# PC104-52-52.net
KiCad netlist of a schematic drawn in Altium Designer
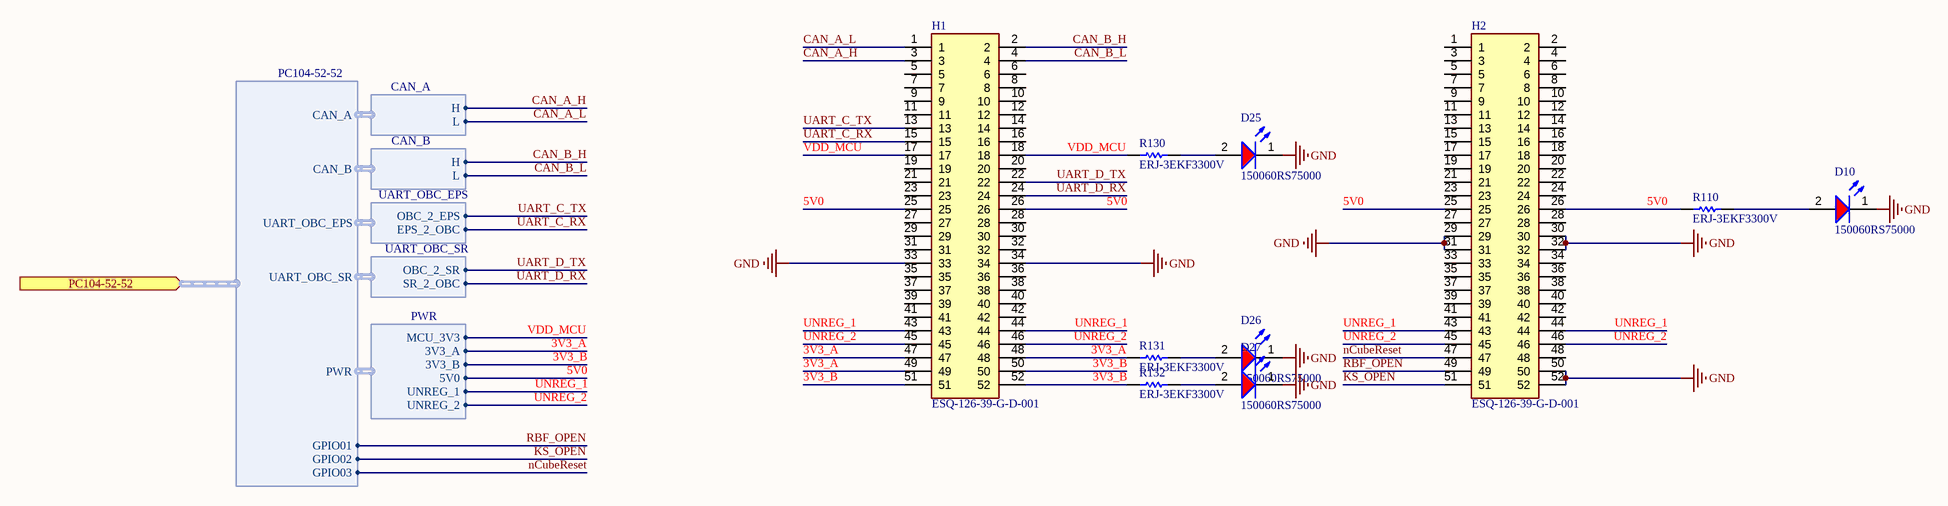
[diagram p0: PC104-52-52.SchDoc]

(export (version "E")
  (design (tool "Eeschema 10.0.6"))
  (components
    (comp (ref "D10")
      (value "150060RS75000")
      (footprint "WL-SMCW_0603_150060xx75000")
      (description "LED Low-Power Uni-Color Red 630nm 2V 2-Pin Chip 0603(1608Metric) T/R")
      (libsource (lib "Altium Content Vault") (part "LED_Red_2A-1K"))
    )
    (comp (ref "D25")
      (value "150060RS75000")
      (footprint "WL-SMCW_0603_150060xx75000")
      (description "LED Low-Power Uni-Color Red 630nm 2V 2-Pin Chip 0603(1608Metric) T/R")
      (libsource (lib "Altium Content Vault") (part "LED_Red_2A-1K"))
    )
    (comp (ref "D26")
      (value "150060RS75000")
      (footprint "WL-SMCW_0603_150060xx75000")
      (description "LED Low-Power Uni-Color Red 630nm 2V 2-Pin Chip 0603(1608Metric) T/R")
      (libsource (lib "Altium Content Vault") (part "LED_Red_2A-1K"))
    )
    (comp (ref "D27")
      (value "150060RS75000")
      (footprint "WL-SMCW_0603_150060xx75000")
      (description "LED Low-Power Uni-Color Red 630nm 2V 2-Pin Chip 0603(1608Metric) T/R")
      (libsource (lib "Altium Content Vault") (part "LED_Red_2A-1K"))
    )
    (comp (ref "H1")
      (value "ESQ-126-39-G-D-001")
      (footprint "RHDR52W64P254_2X26_6654X495X1135P")
      (description "PC / 104 Connectors Elevated Socket Strip")
      (fields (field (name "MOUSER PART NUMBER") "200-ESQ12639GD001"))
      (libsource (lib "Hitesh Bhoyar") (part "ESQ-126-39-G-D-001"))
    )
    (comp (ref "H2")
      (value "ESQ-126-39-G-D-001")
      (footprint "RHDR52W64P254_2X26_6654X495X1135P")
      (description "PC / 104 Connectors Elevated Socket Strip")
      (fields (field (name "MOUSER PART NUMBER") "200-ESQ12639GD001"))
      (libsource (lib "Hitesh Bhoyar") (part "ESQ-126-39-G-D-001"))
    )
    (comp (ref "R110")
      (value "ERJ-3EKF3300V")
      (footprint "RESC1608X55X30LL15T15")
      (description "Chip Resistor, 330 Ohm, +/- 1%, 0.1 W, -55 to 155 degC, 0603 (1608 Metric), RoHS, Tape and Reel")
      (libsource (lib "Altium Content Vault") (part "RES-2"))
    )
    (comp (ref "R130")
      (value "ERJ-3EKF3300V")
      (footprint "RESC1608X55X30LL15T15")
      (description "Chip Resistor, 330 Ohm, +/- 1%, 0.1 W, -55 to 155 degC, 0603 (1608 Metric), RoHS, Tape and Reel")
      (libsource (lib "Altium Content Vault") (part "RES-2"))
    )
    (comp (ref "R131")
      (value "ERJ-3EKF3300V")
      (footprint "RESC1608X55X30LL15T15")
      (description "Chip Resistor, 330 Ohm, +/- 1%, 0.1 W, -55 to 155 degC, 0603 (1608 Metric), RoHS, Tape and Reel")
      (libsource (lib "Altium Content Vault") (part "RES-2"))
    )
    (comp (ref "R132")
      (value "ERJ-3EKF3300V")
      (footprint "RESC1608X55X30LL15T15")
      (description "Chip Resistor, 330 Ohm, +/- 1%, 0.1 W, -55 to 155 degC, 0603 (1608 Metric), RoHS, Tape and Reel")
      (libsource (lib "Altium Content Vault") (part "RES-2"))
    )
  )
  (nets
    (net (code "7") (name "/3V3_A") (class "Default")
      (node (ref "H1") (pin "47") (pinfunction "47_47") (pintype "passive"))
      (node (ref "H1") (pin "48") (pinfunction "48_48") (pintype "passive"))
      (node (ref "H1") (pin "49") (pinfunction "49_49") (pintype "passive"))
      (node (ref "R131") (pin "1") (pinfunction "1_1") (pintype "passive"))
    )
    (net (code "8") (name "/3V3_B") (class "Default")
      (node (ref "H1") (pin "50") (pinfunction "50_50") (pintype "passive"))
      (node (ref "H1") (pin "51") (pinfunction "51_51") (pintype "passive"))
      (node (ref "H1") (pin "52") (pinfunction "52_52") (pintype "passive"))
      (node (ref "R132") (pin "1") (pinfunction "1_1") (pintype "passive"))
    )
    (net (code "9") (name "/5V0") (class "Default")
      (node (ref "H1") (pin "25") (pinfunction "25_25") (pintype "passive"))
      (node (ref "H1") (pin "26") (pinfunction "26_26") (pintype "passive"))
      (node (ref "H2") (pin "25") (pinfunction "25_25") (pintype "passive"))
      (node (ref "H2") (pin "26") (pinfunction "26_26") (pintype "passive"))
      (node (ref "R110") (pin "1") (pinfunction "1_1") (pintype "passive"))
    )
    (net (code "10") (name "/CAN_A_H") (class "Default")
      (node (ref "H1") (pin "3") (pinfunction "3_3") (pintype "passive"))
    )
    (net (code "11") (name "/CAN_A_L") (class "Default")
      (node (ref "H1") (pin "1") (pinfunction "1_1") (pintype "passive"))
    )
    (net (code "12") (name "/CAN_B_H") (class "Default")
      (node (ref "H1") (pin "2") (pinfunction "2_2") (pintype "passive"))
    )
    (net (code "13") (name "/CAN_B_L") (class "Default")
      (node (ref "H1") (pin "4") (pinfunction "4_4") (pintype "passive"))
    )
    (net (code "14") (name "/KS_OPEN") (class "Default")
      (node (ref "H2") (pin "51") (pinfunction "51_51") (pintype "passive"))
    )
    (net (code "16") (name "/RBF_OPEN") (class "Default")
      (node (ref "H2") (pin "49") (pinfunction "49_49") (pintype "passive"))
    )
    (net (code "17") (name "/UART_C_RX") (class "Default")
      (node (ref "H1") (pin "15") (pinfunction "15_15") (pintype "passive"))
    )
    (net (code "18") (name "/UART_C_TX") (class "Default")
      (node (ref "H1") (pin "13") (pinfunction "13_13") (pintype "passive"))
    )
    (net (code "19") (name "/UART_D_RX") (class "Default")
      (node (ref "H1") (pin "24") (pinfunction "24_24") (pintype "passive"))
    )
    (net (code "20") (name "/UART_D_TX") (class "Default")
      (node (ref "H1") (pin "22") (pinfunction "22_22") (pintype "passive"))
    )
    (net (code "21") (name "/UNREG_1") (class "Default")
      (node (ref "H1") (pin "43") (pinfunction "43_43") (pintype "passive"))
      (node (ref "H1") (pin "44") (pinfunction "44_44") (pintype "passive"))
      (node (ref "H2") (pin "43") (pinfunction "43_43") (pintype "passive"))
      (node (ref "H2") (pin "44") (pinfunction "44_44") (pintype "passive"))
    )
    (net (code "22") (name "/UNREG_2") (class "Default")
      (node (ref "H1") (pin "45") (pinfunction "45_45") (pintype "passive"))
      (node (ref "H1") (pin "46") (pinfunction "46_46") (pintype "passive"))
      (node (ref "H2") (pin "45") (pinfunction "45_45") (pintype "passive"))
      (node (ref "H2") (pin "46") (pinfunction "46_46") (pintype "passive"))
    )
    (net (code "23") (name "/VDD_MCU") (class "Default")
      (node (ref "H1") (pin "17") (pinfunction "17_17") (pintype "passive"))
      (node (ref "H1") (pin "18") (pinfunction "18_18") (pintype "passive"))
      (node (ref "R130") (pin "1") (pinfunction "1_1") (pintype "passive"))
    )
    (net (code "24") (name "/nCubeReset") (class "Default")
      (node (ref "H2") (pin "47") (pinfunction "47_47") (pintype "passive"))
    )
    (net (code "30") (name "GND") (class "Default")
      (node (ref "D10") (pin "1") (pinfunction "K_1") (pintype "passive"))
      (node (ref "D25") (pin "1") (pinfunction "K_1") (pintype "passive"))
      (node (ref "D26") (pin "1") (pinfunction "K_1") (pintype "passive"))
      (node (ref "D27") (pin "1") (pinfunction "K_1") (pintype "passive"))
      (node (ref "H1") (pin "33") (pinfunction "33_33") (pintype "passive"))
      (node (ref "H1") (pin "34") (pinfunction "34_34") (pintype "passive"))
      (node (ref "H2") (pin "29") (pinfunction "29_29") (pintype "passive"))
      (node (ref "H2") (pin "30") (pinfunction "30_30") (pintype "passive"))
      (node (ref "H2") (pin "31") (pinfunction "31_31") (pintype "passive"))
      (node (ref "H2") (pin "32") (pinfunction "32_32") (pintype "passive"))
      (node (ref "H2") (pin "50") (pinfunction "50_50") (pintype "passive"))
      (node (ref "H2") (pin "52") (pinfunction "52_52") (pintype "passive"))
    )
    (net (code "31") (name "Net-(D10-A)") (class "Default")
      (node (ref "D10") (pin "2") (pinfunction "A_2") (pintype "passive"))
      (node (ref "R110") (pin "2") (pinfunction "2_2") (pintype "passive"))
    )
    (net (code "32") (name "Net-(D25-A)") (class "Default")
      (node (ref "D25") (pin "2") (pinfunction "A_2") (pintype "passive"))
      (node (ref "R130") (pin "2") (pinfunction "2_2") (pintype "passive"))
    )
    (net (code "33") (name "Net-(D26-A)") (class "Default")
      (node (ref "D26") (pin "2") (pinfunction "A_2") (pintype "passive"))
      (node (ref "R131") (pin "2") (pinfunction "2_2") (pintype "passive"))
    )
    (net (code "34") (name "Net-(D27-A)") (class "Default")
      (node (ref "D27") (pin "2") (pinfunction "A_2") (pintype "passive"))
      (node (ref "R132") (pin "2") (pinfunction "2_2") (pintype "passive"))
    )
    (net (code "35") (name "unconnected-(H1-Pad5)") (class "Default")
      (node (ref "H1") (pin "5") (pinfunction "5_5") (pintype "passive"))
    )
    (net (code "36") (name "unconnected-(H1-Pad6)") (class "Default")
      (node (ref "H1") (pin "6") (pinfunction "6_6") (pintype "passive"))
    )
    (net (code "37") (name "unconnected-(H1-Pad7)") (class "Default")
      (node (ref "H1") (pin "7") (pinfunction "7_7") (pintype "passive"))
    )
    (net (code "38") (name "unconnected-(H1-Pad8)") (class "Default")
      (node (ref "H1") (pin "8") (pinfunction "8_8") (pintype "passive"))
    )
    (net (code "39") (name "unconnected-(H1-Pad9)") (class "Default")
      (node (ref "H1") (pin "9") (pinfunction "9_9") (pintype "passive"))
    )
    (net (code "40") (name "unconnected-(H1-Pad10)") (class "Default")
      (node (ref "H1") (pin "10") (pinfunction "10_10") (pintype "passive"))
    )
    (net (code "41") (name "unconnected-(H1-Pad11)") (class "Default")
      (node (ref "H1") (pin "11") (pinfunction "11_11") (pintype "passive"))
    )
    (net (code "42") (name "unconnected-(H1-Pad12)") (class "Default")
      (node (ref "H1") (pin "12") (pinfunction "12_12") (pintype "passive"))
    )
    (net (code "43") (name "unconnected-(H1-Pad14)") (class "Default")
      (node (ref "H1") (pin "14") (pinfunction "14_14") (pintype "passive"))
    )
    (net (code "44") (name "unconnected-(H1-Pad16)") (class "Default")
      (node (ref "H1") (pin "16") (pinfunction "16_16") (pintype "passive"))
    )
    (net (code "45") (name "unconnected-(H1-Pad19)") (class "Default")
      (node (ref "H1") (pin "19") (pinfunction "19_19") (pintype "passive"))
    )
    (net (code "46") (name "unconnected-(H1-Pad20)") (class "Default")
      (node (ref "H1") (pin "20") (pinfunction "20_20") (pintype "passive"))
    )
    (net (code "47") (name "unconnected-(H1-Pad21)") (class "Default")
      (node (ref "H1") (pin "21") (pinfunction "21_21") (pintype "passive"))
    )
    (net (code "48") (name "unconnected-(H1-Pad23)") (class "Default")
      (node (ref "H1") (pin "23") (pinfunction "23_23") (pintype "passive"))
    )
    (net (code "49") (name "unconnected-(H1-Pad27)") (class "Default")
      (node (ref "H1") (pin "27") (pinfunction "27_27") (pintype "passive"))
    )
    (net (code "50") (name "unconnected-(H1-Pad28)") (class "Default")
      (node (ref "H1") (pin "28") (pinfunction "28_28") (pintype "passive"))
    )
    (net (code "51") (name "unconnected-(H1-Pad29)") (class "Default")
      (node (ref "H1") (pin "29") (pinfunction "29_29") (pintype "passive"))
    )
    (net (code "52") (name "unconnected-(H1-Pad30)") (class "Default")
      (node (ref "H1") (pin "30") (pinfunction "30_30") (pintype "passive"))
    )
    (net (code "53") (name "unconnected-(H1-Pad31)") (class "Default")
      (node (ref "H1") (pin "31") (pinfunction "31_31") (pintype "passive"))
    )
    (net (code "54") (name "unconnected-(H1-Pad32)") (class "Default")
      (node (ref "H1") (pin "32") (pinfunction "32_32") (pintype "passive"))
    )
    (net (code "55") (name "unconnected-(H1-Pad35)") (class "Default")
      (node (ref "H1") (pin "35") (pinfunction "35_35") (pintype "passive"))
    )
    (net (code "56") (name "unconnected-(H1-Pad36)") (class "Default")
      (node (ref "H1") (pin "36") (pinfunction "36_36") (pintype "passive"))
    )
    (net (code "57") (name "unconnected-(H1-Pad37)") (class "Default")
      (node (ref "H1") (pin "37") (pinfunction "37_37") (pintype "passive"))
    )
    (net (code "58") (name "unconnected-(H1-Pad38)") (class "Default")
      (node (ref "H1") (pin "38") (pinfunction "38_38") (pintype "passive"))
    )
    (net (code "59") (name "unconnected-(H1-Pad39)") (class "Default")
      (node (ref "H1") (pin "39") (pinfunction "39_39") (pintype "passive"))
    )
    (net (code "60") (name "unconnected-(H1-Pad40)") (class "Default")
      (node (ref "H1") (pin "40") (pinfunction "40_40") (pintype "passive"))
    )
    (net (code "61") (name "unconnected-(H1-Pad41)") (class "Default")
      (node (ref "H1") (pin "41") (pinfunction "41_41") (pintype "passive"))
    )
    (net (code "62") (name "unconnected-(H1-Pad42)") (class "Default")
      (node (ref "H1") (pin "42") (pinfunction "42_42") (pintype "passive"))
    )
    (net (code "63") (name "unconnected-(H2-Pad1)") (class "Default")
      (node (ref "H2") (pin "1") (pinfunction "1_1") (pintype "passive"))
    )
    (net (code "64") (name "unconnected-(H2-Pad2)") (class "Default")
      (node (ref "H2") (pin "2") (pinfunction "2_2") (pintype "passive"))
    )
    (net (code "65") (name "unconnected-(H2-Pad3)") (class "Default")
      (node (ref "H2") (pin "3") (pinfunction "3_3") (pintype "passive"))
    )
    (net (code "66") (name "unconnected-(H2-Pad4)") (class "Default")
      (node (ref "H2") (pin "4") (pinfunction "4_4") (pintype "passive"))
    )
    (net (code "67") (name "unconnected-(H2-Pad5)") (class "Default")
      (node (ref "H2") (pin "5") (pinfunction "5_5") (pintype "passive"))
    )
    (net (code "68") (name "unconnected-(H2-Pad6)") (class "Default")
      (node (ref "H2") (pin "6") (pinfunction "6_6") (pintype "passive"))
    )
    (net (code "69") (name "unconnected-(H2-Pad7)") (class "Default")
      (node (ref "H2") (pin "7") (pinfunction "7_7") (pintype "passive"))
    )
    (net (code "70") (name "unconnected-(H2-Pad8)") (class "Default")
      (node (ref "H2") (pin "8") (pinfunction "8_8") (pintype "passive"))
    )
    (net (code "71") (name "unconnected-(H2-Pad9)") (class "Default")
      (node (ref "H2") (pin "9") (pinfunction "9_9") (pintype "passive"))
    )
    (net (code "72") (name "unconnected-(H2-Pad10)") (class "Default")
      (node (ref "H2") (pin "10") (pinfunction "10_10") (pintype "passive"))
    )
    (net (code "73") (name "unconnected-(H2-Pad11)") (class "Default")
      (node (ref "H2") (pin "11") (pinfunction "11_11") (pintype "passive"))
    )
    (net (code "74") (name "unconnected-(H2-Pad12)") (class "Default")
      (node (ref "H2") (pin "12") (pinfunction "12_12") (pintype "passive"))
    )
    (net (code "75") (name "unconnected-(H2-Pad13)") (class "Default")
      (node (ref "H2") (pin "13") (pinfunction "13_13") (pintype "passive"))
    )
    (net (code "76") (name "unconnected-(H2-Pad14)") (class "Default")
      (node (ref "H2") (pin "14") (pinfunction "14_14") (pintype "passive"))
    )
    (net (code "77") (name "unconnected-(H2-Pad15)") (class "Default")
      (node (ref "H2") (pin "15") (pinfunction "15_15") (pintype "passive"))
    )
    (net (code "78") (name "unconnected-(H2-Pad16)") (class "Default")
      (node (ref "H2") (pin "16") (pinfunction "16_16") (pintype "passive"))
    )
    (net (code "79") (name "unconnected-(H2-Pad17)") (class "Default")
      (node (ref "H2") (pin "17") (pinfunction "17_17") (pintype "passive"))
    )
    (net (code "80") (name "unconnected-(H2-Pad18)") (class "Default")
      (node (ref "H2") (pin "18") (pinfunction "18_18") (pintype "passive"))
    )
    (net (code "81") (name "unconnected-(H2-Pad19)") (class "Default")
      (node (ref "H2") (pin "19") (pinfunction "19_19") (pintype "passive"))
    )
    (net (code "82") (name "unconnected-(H2-Pad20)") (class "Default")
      (node (ref "H2") (pin "20") (pinfunction "20_20") (pintype "passive"))
    )
    (net (code "83") (name "unconnected-(H2-Pad21)") (class "Default")
      (node (ref "H2") (pin "21") (pinfunction "21_21") (pintype "passive"))
    )
    (net (code "84") (name "unconnected-(H2-Pad22)") (class "Default")
      (node (ref "H2") (pin "22") (pinfunction "22_22") (pintype "passive"))
    )
    (net (code "85") (name "unconnected-(H2-Pad23)") (class "Default")
      (node (ref "H2") (pin "23") (pinfunction "23_23") (pintype "passive"))
    )
    (net (code "86") (name "unconnected-(H2-Pad24)") (class "Default")
      (node (ref "H2") (pin "24") (pinfunction "24_24") (pintype "passive"))
    )
    (net (code "87") (name "unconnected-(H2-Pad27)") (class "Default")
      (node (ref "H2") (pin "27") (pinfunction "27_27") (pintype "passive"))
    )
    (net (code "88") (name "unconnected-(H2-Pad28)") (class "Default")
      (node (ref "H2") (pin "28") (pinfunction "28_28") (pintype "passive"))
    )
    (net (code "89") (name "unconnected-(H2-Pad33)") (class "Default")
      (node (ref "H2") (pin "33") (pinfunction "33_33") (pintype "passive"))
    )
    (net (code "90") (name "unconnected-(H2-Pad34)") (class "Default")
      (node (ref "H2") (pin "34") (pinfunction "34_34") (pintype "passive"))
    )
    (net (code "91") (name "unconnected-(H2-Pad35)") (class "Default")
      (node (ref "H2") (pin "35") (pinfunction "35_35") (pintype "passive"))
    )
    (net (code "92") (name "unconnected-(H2-Pad36)") (class "Default")
      (node (ref "H2") (pin "36") (pinfunction "36_36") (pintype "passive"))
    )
    (net (code "93") (name "unconnected-(H2-Pad37)") (class "Default")
      (node (ref "H2") (pin "37") (pinfunction "37_37") (pintype "passive"))
    )
    (net (code "94") (name "unconnected-(H2-Pad38)") (class "Default")
      (node (ref "H2") (pin "38") (pinfunction "38_38") (pintype "passive"))
    )
    (net (code "95") (name "unconnected-(H2-Pad39)") (class "Default")
      (node (ref "H2") (pin "39") (pinfunction "39_39") (pintype "passive"))
    )
    (net (code "96") (name "unconnected-(H2-Pad40)") (class "Default")
      (node (ref "H2") (pin "40") (pinfunction "40_40") (pintype "passive"))
    )
    (net (code "97") (name "unconnected-(H2-Pad41)") (class "Default")
      (node (ref "H2") (pin "41") (pinfunction "41_41") (pintype "passive"))
    )
    (net (code "98") (name "unconnected-(H2-Pad42)") (class "Default")
      (node (ref "H2") (pin "42") (pinfunction "42_42") (pintype "passive"))
    )
    (net (code "99") (name "unconnected-(H2-Pad48)") (class "Default")
      (node (ref "H2") (pin "48") (pinfunction "48_48") (pintype "passive"))
    )
  )
)
